# openTPM-v13.net
KiCad netlist of a schematic drawn in EAGLE
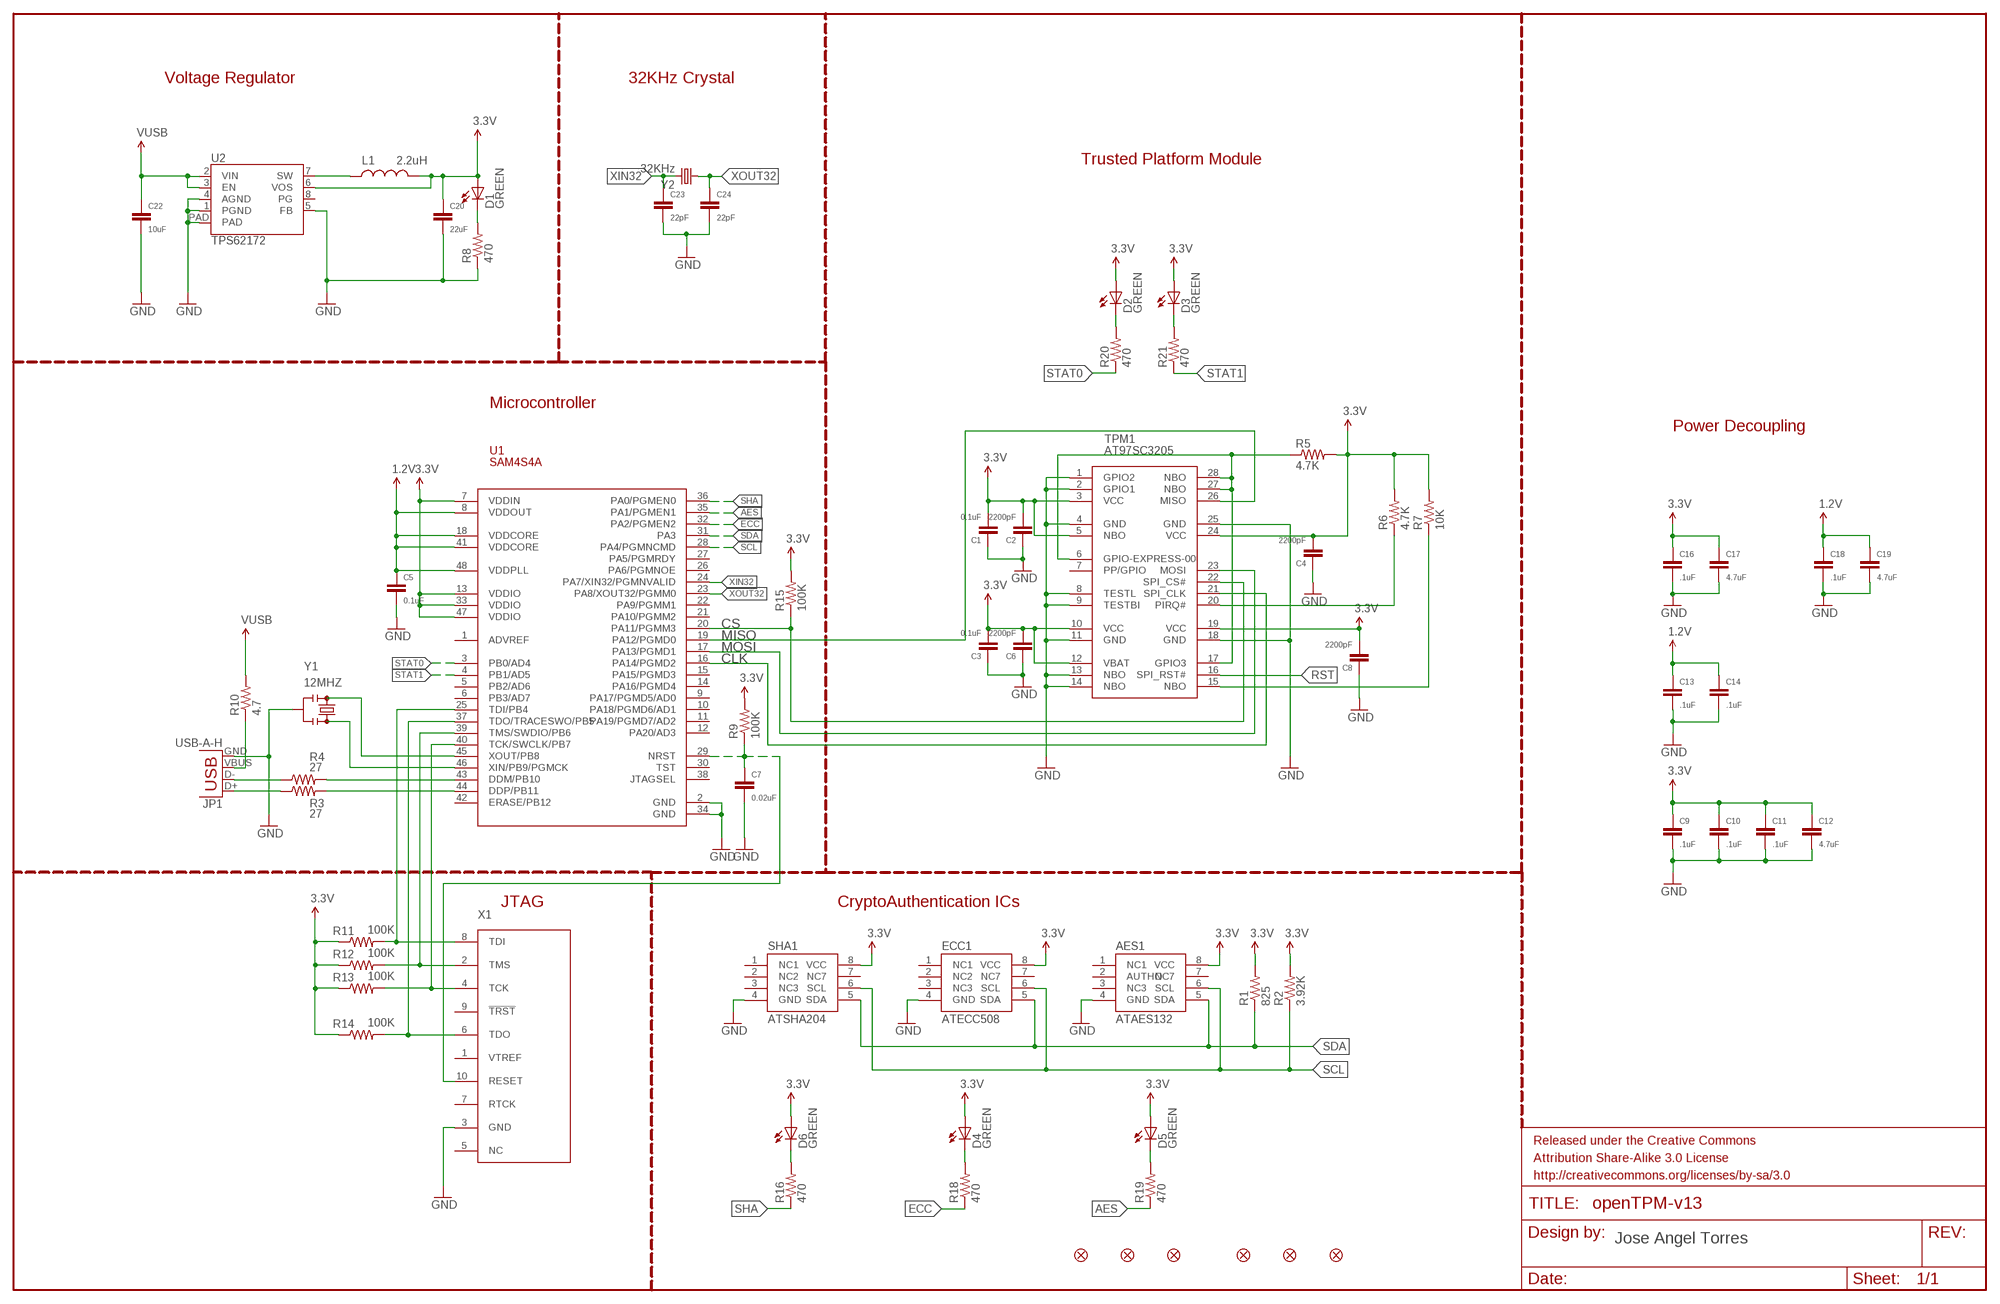
[diagram p0: schematic, sheet 1]

(export (version "E")
  (design (tool "Eeschema 10.0.6"))
  (components
    (comp (ref "AES1")
      (value "ATAES132")
      (footprint "eagle-import:CRYPTOTRONIX_SOIC8")
      (libsource (lib "eagle-import") (part "CRYPTOTRONIX_ATAES132"))
    )
    (comp (ref "C1")
      (value "0.1uF")
      (footprint "eagle-import:0201")
      (libsource (lib "eagle-import") (part "CAPACITOR.0201"))
    )
    (comp (ref "C2")
      (value "2200pF")
      (footprint "eagle-import:0201")
      (libsource (lib "eagle-import") (part "CAPACITOR.0201"))
    )
    (comp (ref "C3")
      (value "0.1uF")
      (footprint "eagle-import:0201")
      (libsource (lib "eagle-import") (part "CAPACITOR.0201"))
    )
    (comp (ref "C4")
      (value "2200pF")
      (footprint "eagle-import:0201")
      (libsource (lib "eagle-import") (part "CAPACITOR.0201"))
    )
    (comp (ref "C5")
      (value "0.1uF")
      (footprint "eagle-import:0201")
      (libsource (lib "eagle-import") (part "CAPACITOR.0201"))
    )
    (comp (ref "C6")
      (value "2200pF")
      (footprint "eagle-import:0201")
      (libsource (lib "eagle-import") (part "CAPACITOR.0201"))
    )
    (comp (ref "C7")
      (value "0.02uF")
      (footprint "eagle-import:0201")
      (libsource (lib "eagle-import") (part "CAPACITOR.0201"))
    )
    (comp (ref "C8")
      (value "2200pF")
      (footprint "eagle-import:0201")
      (libsource (lib "eagle-import") (part "CAPACITOR.0201"))
    )
    (comp (ref "C9")
      (value ".1uF")
      (footprint "eagle-import:0201")
      (libsource (lib "eagle-import") (part "CAPACITOR.0201"))
    )
    (comp (ref "C10")
      (value ".1uF")
      (footprint "eagle-import:0201")
      (libsource (lib "eagle-import") (part "CAPACITOR.0201"))
    )
    (comp (ref "C11")
      (value ".1uF")
      (footprint "eagle-import:0201")
      (libsource (lib "eagle-import") (part "CAPACITOR.0201"))
    )
    (comp (ref "C12")
      (value "4.7uF")
      (footprint "eagle-import:0402")
      (libsource (lib "eagle-import") (part "CAPACITOR.0402"))
    )
    (comp (ref "C13")
      (value ".1uF")
      (footprint "eagle-import:0201")
      (libsource (lib "eagle-import") (part "CAPACITOR.0201"))
    )
    (comp (ref "C14")
      (value ".1uF")
      (footprint "eagle-import:0201")
      (libsource (lib "eagle-import") (part "CAPACITOR.0201"))
    )
    (comp (ref "C16")
      (value ".1uF")
      (footprint "eagle-import:0201")
      (libsource (lib "eagle-import") (part "CAPACITOR.0201"))
    )
    (comp (ref "C17")
      (value "4.7uF")
      (footprint "eagle-import:0402")
      (libsource (lib "eagle-import") (part "CAPACITOR.0402"))
    )
    (comp (ref "C18")
      (value ".1uF")
      (footprint "eagle-import:0201")
      (libsource (lib "eagle-import") (part "CAPACITOR.0201"))
    )
    (comp (ref "C19")
      (value "4.7uF")
      (footprint "eagle-import:0402")
      (libsource (lib "eagle-import") (part "CAPACITOR.0402"))
    )
    (comp (ref "C20")
      (value "22uF")
      (footprint "eagle-import:0603")
      (libsource (lib "eagle-import") (part "CAPACITOR.0603"))
    )
    (comp (ref "C22")
      (value "10uF")
      (footprint "eagle-import:0402")
      (libsource (lib "eagle-import") (part "CAPACITOR.0402"))
    )
    (comp (ref "C23")
      (value "22pF")
      (footprint "eagle-import:0201")
      (libsource (lib "eagle-import") (part "CAPACITOR.0201"))
    )
    (comp (ref "C24")
      (value "22pF")
      (footprint "eagle-import:0201")
      (libsource (lib "eagle-import") (part "CAPACITOR.0201"))
    )
    (comp (ref "D1")
      (value "GREEN")
      (footprint "eagle-import:SPARKFUN-LED_LED-0603")
      (libsource (lib "eagle-import") (part "SPARKFUN-LED_LED-GREEN0603"))
    )
    (comp (ref "D2")
      (value "GREEN")
      (footprint "eagle-import:SPARKFUN-LED_LED-0603")
      (libsource (lib "eagle-import") (part "SPARKFUN-LED_LED-GREEN0603"))
    )
    (comp (ref "D3")
      (value "GREEN")
      (footprint "eagle-import:SPARKFUN-LED_LED-0603")
      (libsource (lib "eagle-import") (part "SPARKFUN-LED_LED-GREEN0603"))
    )
    (comp (ref "D4")
      (value "GREEN")
      (footprint "eagle-import:SPARKFUN-LED_LED-0603")
      (libsource (lib "eagle-import") (part "SPARKFUN-LED_LED-GREEN0603"))
    )
    (comp (ref "D5")
      (value "GREEN")
      (footprint "eagle-import:SPARKFUN-LED_LED-0603")
      (libsource (lib "eagle-import") (part "SPARKFUN-LED_LED-GREEN0603"))
    )
    (comp (ref "D6")
      (value "GREEN")
      (footprint "eagle-import:SPARKFUN-LED_LED-0603")
      (libsource (lib "eagle-import") (part "SPARKFUN-LED_LED-GREEN0603"))
    )
    (comp (ref "ECC1")
      (value "ATECC508")
      (footprint "eagle-import:CRYPTOTRONIX_SOIC8")
      (libsource (lib "eagle-import") (part "ATECC508"))
    )
    (comp (ref "FID1")
      (value "SPARKFUN-AESTHETICS_FIDUCIAL1X2")
      (footprint "eagle-import:SPARKFUN-AESTHETICS_FIDUCIAL-1X2")
      (libsource (lib "eagle-import") (part "SPARKFUN-AESTHETICS_FIDUCIAL1X2"))
    )
    (comp (ref "FID2")
      (value "SPARKFUN-AESTHETICS_FIDUCIAL1X2")
      (footprint "eagle-import:SPARKFUN-AESTHETICS_FIDUCIAL-1X2")
      (libsource (lib "eagle-import") (part "SPARKFUN-AESTHETICS_FIDUCIAL1X2"))
    )
    (comp (ref "FID3")
      (value "SPARKFUN-AESTHETICS_FIDUCIAL1X2")
      (footprint "eagle-import:SPARKFUN-AESTHETICS_FIDUCIAL-1X2")
      (libsource (lib "eagle-import") (part "SPARKFUN-AESTHETICS_FIDUCIAL1X2"))
    )
    (comp (ref "FID4")
      (value "SPARKFUN-AESTHETICS_FIDUCIAL1X2")
      (footprint "eagle-import:SPARKFUN-AESTHETICS_FIDUCIAL-1X2")
      (libsource (lib "eagle-import") (part "SPARKFUN-AESTHETICS_FIDUCIAL1X2"))
    )
    (comp (ref "FID5")
      (value "SPARKFUN-AESTHETICS_FIDUCIAL1X2")
      (footprint "eagle-import:SPARKFUN-AESTHETICS_FIDUCIAL-1X2")
      (libsource (lib "eagle-import") (part "SPARKFUN-AESTHETICS_FIDUCIAL1X2"))
    )
    (comp (ref "FID6")
      (value "SPARKFUN-AESTHETICS_FIDUCIAL1X2")
      (footprint "eagle-import:SPARKFUN-AESTHETICS_FIDUCIAL-1X2")
      (libsource (lib "eagle-import") (part "SPARKFUN-AESTHETICS_FIDUCIAL1X2"))
    )
    (comp (ref "JP1")
      (value "USB-A-H")
      (footprint "eagle-import:USB-A-H")
      (libsource (lib "eagle-import") (part "USB-A-H"))
    )
    (comp (ref "L1")
      (value "2.2uH")
      (footprint "eagle-import:C0402")
      (libsource (lib "eagle-import") (part "INDUCTOR0402"))
    )
    (comp (ref "R1")
      (value "825")
      (footprint "eagle-import:0201")
      (libsource (lib "eagle-import") (part "RESISTOR.0201"))
    )
    (comp (ref "R2")
      (value "3.92K")
      (footprint "eagle-import:0201")
      (libsource (lib "eagle-import") (part "RESISTOR.0201"))
    )
    (comp (ref "R3")
      (value "27")
      (footprint "eagle-import:0402")
      (libsource (lib "eagle-import") (part "RESISTOR.0402"))
    )
    (comp (ref "R4")
      (value "27")
      (footprint "eagle-import:0402")
      (libsource (lib "eagle-import") (part "RESISTOR.0402"))
    )
    (comp (ref "R5")
      (value "4.7K")
      (footprint "eagle-import:0201")
      (libsource (lib "eagle-import") (part "RESISTOR.0201"))
    )
    (comp (ref "R6")
      (value "4.7K")
      (footprint "eagle-import:0201")
      (libsource (lib "eagle-import") (part "RESISTOR.0201"))
    )
    (comp (ref "R7")
      (value "10K")
      (footprint "eagle-import:0201")
      (libsource (lib "eagle-import") (part "RESISTOR.0201"))
    )
    (comp (ref "R8")
      (value "470")
      (footprint "eagle-import:0201")
      (libsource (lib "eagle-import") (part "RESISTOR.0201"))
    )
    (comp (ref "R9")
      (value "100K")
      (footprint "eagle-import:0201")
      (libsource (lib "eagle-import") (part "RESISTOR.0201"))
    )
    (comp (ref "R10")
      (value "4.7")
      (footprint "eagle-import:0402")
      (libsource (lib "eagle-import") (part "RESISTOR.0402"))
    )
    (comp (ref "R11")
      (value "100K")
      (footprint "eagle-import:0201")
      (libsource (lib "eagle-import") (part "RESISTOR.0201"))
    )
    (comp (ref "R12")
      (value "100K")
      (footprint "eagle-import:0201")
      (libsource (lib "eagle-import") (part "RESISTOR.0201"))
    )
    (comp (ref "R13")
      (value "100K")
      (footprint "eagle-import:0201")
      (libsource (lib "eagle-import") (part "RESISTOR.0201"))
    )
    (comp (ref "R14")
      (value "100K")
      (footprint "eagle-import:0201")
      (libsource (lib "eagle-import") (part "RESISTOR.0201"))
    )
    (comp (ref "R15")
      (value "100K")
      (footprint "eagle-import:0201")
      (libsource (lib "eagle-import") (part "RESISTOR.0201"))
    )
    (comp (ref "R16")
      (value "470")
      (footprint "eagle-import:0201")
      (libsource (lib "eagle-import") (part "RESISTOR.0201"))
    )
    (comp (ref "R18")
      (value "470")
      (footprint "eagle-import:0201")
      (libsource (lib "eagle-import") (part "RESISTOR.0201"))
    )
    (comp (ref "R19")
      (value "470")
      (footprint "eagle-import:0201")
      (libsource (lib "eagle-import") (part "RESISTOR.0201"))
    )
    (comp (ref "R20")
      (value "470")
      (footprint "eagle-import:0201")
      (libsource (lib "eagle-import") (part "RESISTOR.0201"))
    )
    (comp (ref "R21")
      (value "470")
      (footprint "eagle-import:0201")
      (libsource (lib "eagle-import") (part "RESISTOR.0201"))
    )
    (comp (ref "SHA1")
      (value "ATSHA204")
      (footprint "eagle-import:CRYPTOTRONIX_SOIC8")
      (libsource (lib "eagle-import") (part "CRYPTOTRONIX_ATSHA204"))
    )
    (comp (ref "TPM1")
      (value "AT97SC3205")
      (footprint "eagle-import:TSSOP28")
      (libsource (lib "eagle-import") (part "AT97SC3205"))
    )
    (comp (ref "U1")
      (value "SAM4S4A")
      (footprint "eagle-import:LQFP-48")
      (libsource (lib "eagle-import") (part "SAM4S4A"))
    )
    (comp (ref "U2")
      (value "TPS62172")
      (footprint "eagle-import:WSON-8-PAD")
      (libsource (lib "eagle-import") (part "TPS62172"))
    )
    (comp (ref "X1")
      (value "TC2050-NL-MCP-NL")
      (footprint "eagle-import:TC2030-MCP-NL")
      (libsource (lib "eagle-import") (part "TC2050-NL-MCP-NL"))
    )
    (comp (ref "Y1")
      (value "12MHZ")
      (footprint "eagle-import:RESONATOR-SMD")
      (libsource (lib "eagle-import") (part "RESONATOR12MHZ"))
    )
    (comp (ref "Y2")
      (value "32KHz")
      (footprint "eagle-import:CRYSTAL-32KHZ-SMD_EPSON_MC146")
      (libsource (lib "eagle-import") (part "CRYSTALEPSONMC146"))
    )
  )
  (nets
    (net (code "1") (name "/CLK") (class "Default")
      (node (ref "TPM1") (pin "21") (pinfunction "SPI_CLK_21") (pintype "bidirectional"))
      (node (ref "U1") (pin "16") (pinfunction "PA14/PGMD2_16") (pintype "bidirectional"))
    )
    (net (code "2") (name "/CS") (class "Default")
      (node (ref "R15") (pin "1") (pinfunction "1_1") (pintype "passive"))
      (node (ref "TPM1") (pin "22") (pinfunction "SPI_CS#_22") (pintype "power_in"))
      (node (ref "U1") (pin "20") (pinfunction "PA11/PGMM3_20") (pintype "bidirectional"))
    )
    (net (code "3") (name "/MISO") (class "Default")
      (node (ref "TPM1") (pin "26") (pinfunction "MISO_26") (pintype "power_in"))
      (node (ref "U1") (pin "19") (pinfunction "PA12/PGMD0_19") (pintype "bidirectional"))
    )
    (net (code "4") (name "/MOSI") (class "Default")
      (node (ref "TPM1") (pin "23") (pinfunction "MOSI_23") (pintype "power_in"))
      (node (ref "U1") (pin "17") (pinfunction "PA13/PGMD1_17") (pintype "bidirectional"))
    )
    (net (code "5") (name "1.2V") (class "Default")
      (node (ref "C13") (pin "1") (pinfunction "1_1") (pintype "passive"))
      (node (ref "C14") (pin "1") (pinfunction "1_1") (pintype "passive"))
      (node (ref "C18") (pin "1") (pinfunction "1_1") (pintype "passive"))
      (node (ref "C19") (pin "1") (pinfunction "1_1") (pintype "passive"))
      (node (ref "C5") (pin "1") (pinfunction "1_1") (pintype "passive"))
      (node (ref "U1") (pin "18") (pinfunction "VDDCORE_18") (pintype "bidirectional"))
      (node (ref "U1") (pin "41") (pinfunction "VDDCORE_41") (pintype "bidirectional"))
      (node (ref "U1") (pin "48") (pinfunction "VDDPLL_48") (pintype "bidirectional"))
      (node (ref "U1") (pin "8") (pinfunction "VDDOUT_8") (pintype "bidirectional"))
    )
    (net (code "6") (name "3.3V") (class "Default")
      (node (ref "AES1") (pin "8") (pinfunction "VCC_8") (pintype "power_in"))
      (node (ref "C1") (pin "2") (pinfunction "2_2") (pintype "passive"))
      (node (ref "C10") (pin "1") (pinfunction "1_1") (pintype "passive"))
      (node (ref "C11") (pin "1") (pinfunction "1_1") (pintype "passive"))
      (node (ref "C12") (pin "1") (pinfunction "1_1") (pintype "passive"))
      (node (ref "C16") (pin "1") (pinfunction "1_1") (pintype "passive"))
      (node (ref "C17") (pin "1") (pinfunction "1_1") (pintype "passive"))
      (node (ref "C2") (pin "2") (pinfunction "2_2") (pintype "passive"))
      (node (ref "C20") (pin "1") (pinfunction "1_1") (pintype "passive"))
      (node (ref "C3") (pin "2") (pinfunction "2_2") (pintype "passive"))
      (node (ref "C4") (pin "2") (pinfunction "2_2") (pintype "passive"))
      (node (ref "C6") (pin "2") (pinfunction "2_2") (pintype "passive"))
      (node (ref "C8") (pin "2") (pinfunction "2_2") (pintype "passive"))
      (node (ref "C9") (pin "1") (pinfunction "1_1") (pintype "passive"))
      (node (ref "D1") (pin "A") (pinfunction "A_A") (pintype "passive"))
      (node (ref "D2") (pin "A") (pinfunction "A_A") (pintype "passive"))
      (node (ref "D3") (pin "A") (pinfunction "A_A") (pintype "passive"))
      (node (ref "D4") (pin "A") (pinfunction "A_A") (pintype "passive"))
      (node (ref "D5") (pin "A") (pinfunction "A_A") (pintype "passive"))
      (node (ref "D6") (pin "A") (pinfunction "A_A") (pintype "passive"))
      (node (ref "ECC1") (pin "8") (pinfunction "VCC_8") (pintype "power_in"))
      (node (ref "L1") (pin "2") (pinfunction "2_2") (pintype "passive"))
      (node (ref "R1") (pin "2") (pinfunction "2_2") (pintype "passive"))
      (node (ref "R11") (pin "1") (pinfunction "1_1") (pintype "passive"))
      (node (ref "R12") (pin "1") (pinfunction "1_1") (pintype "passive"))
      (node (ref "R13") (pin "1") (pinfunction "1_1") (pintype "passive"))
      (node (ref "R14") (pin "1") (pinfunction "1_1") (pintype "passive"))
      (node (ref "R15") (pin "2") (pinfunction "2_2") (pintype "passive"))
      (node (ref "R2") (pin "2") (pinfunction "2_2") (pintype "passive"))
      (node (ref "R5") (pin "2") (pinfunction "2_2") (pintype "passive"))
      (node (ref "R6") (pin "2") (pinfunction "2_2") (pintype "passive"))
      (node (ref "R7") (pin "2") (pinfunction "2_2") (pintype "passive"))
      (node (ref "R9") (pin "2") (pinfunction "2_2") (pintype "passive"))
      (node (ref "SHA1") (pin "8") (pinfunction "VCC_8") (pintype "power_in"))
      (node (ref "TPM1") (pin "10") (pinfunction "VCC_10") (pintype "power_in"))
      (node (ref "TPM1") (pin "12") (pinfunction "VBAT_12") (pintype "bidirectional"))
      (node (ref "TPM1") (pin "19") (pinfunction "VCC_19") (pintype "power_in"))
      (node (ref "TPM1") (pin "24") (pinfunction "VCC_24") (pintype "power_in"))
      (node (ref "TPM1") (pin "3") (pinfunction "VCC_3") (pintype "power_in"))
      (node (ref "TPM1") (pin "5") (pinfunction "NBO_5") (pintype "bidirectional"))
      (node (ref "U1") (pin "13") (pinfunction "VDDIO_13") (pintype "bidirectional"))
      (node (ref "U1") (pin "33") (pinfunction "VDDIO_33") (pintype "bidirectional"))
      (node (ref "U1") (pin "47") (pinfunction "VDDIO_47") (pintype "bidirectional"))
      (node (ref "U1") (pin "7") (pinfunction "VDDIN_7") (pintype "bidirectional"))
      (node (ref "U2") (pin "6") (pinfunction "VOS_6") (pintype "bidirectional"))
    )
    (net (code "7") (name "AES") (class "Default")
      (node (ref "R19") (pin "1") (pinfunction "1_1") (pintype "passive"))
      (node (ref "U1") (pin "35") (pinfunction "PA1/PGMEN1_35") (pintype "bidirectional"))
    )
    (net (code "8") (name "ECC") (class "Default")
      (node (ref "R18") (pin "1") (pinfunction "1_1") (pintype "passive"))
      (node (ref "U1") (pin "32") (pinfunction "PA2/PGMEN2_32") (pintype "bidirectional"))
    )
    (net (code "9") (name "GND") (class "Default")
      (node (ref "AES1") (pin "4") (pinfunction "GND_4") (pintype "power_in"))
      (node (ref "C1") (pin "1") (pinfunction "1_1") (pintype "passive"))
      (node (ref "C10") (pin "2") (pinfunction "2_2") (pintype "passive"))
      (node (ref "C11") (pin "2") (pinfunction "2_2") (pintype "passive"))
      (node (ref "C12") (pin "2") (pinfunction "2_2") (pintype "passive"))
      (node (ref "C13") (pin "2") (pinfunction "2_2") (pintype "passive"))
      (node (ref "C14") (pin "2") (pinfunction "2_2") (pintype "passive"))
      (node (ref "C16") (pin "2") (pinfunction "2_2") (pintype "passive"))
      (node (ref "C17") (pin "2") (pinfunction "2_2") (pintype "passive"))
      (node (ref "C18") (pin "2") (pinfunction "2_2") (pintype "passive"))
      (node (ref "C19") (pin "2") (pinfunction "2_2") (pintype "passive"))
      (node (ref "C2") (pin "1") (pinfunction "1_1") (pintype "passive"))
      (node (ref "C20") (pin "2") (pinfunction "2_2") (pintype "passive"))
      (node (ref "C22") (pin "2") (pinfunction "2_2") (pintype "passive"))
      (node (ref "C23") (pin "2") (pinfunction "2_2") (pintype "passive"))
      (node (ref "C24") (pin "2") (pinfunction "2_2") (pintype "passive"))
      (node (ref "C3") (pin "1") (pinfunction "1_1") (pintype "passive"))
      (node (ref "C4") (pin "1") (pinfunction "1_1") (pintype "passive"))
      (node (ref "C5") (pin "2") (pinfunction "2_2") (pintype "passive"))
      (node (ref "C6") (pin "1") (pinfunction "1_1") (pintype "passive"))
      (node (ref "C7") (pin "2") (pinfunction "2_2") (pintype "passive"))
      (node (ref "C8") (pin "1") (pinfunction "1_1") (pintype "passive"))
      (node (ref "C9") (pin "2") (pinfunction "2_2") (pintype "passive"))
      (node (ref "ECC1") (pin "4") (pinfunction "GND_4") (pintype "power_in"))
      (node (ref "JP1") (pin "GND") (pinfunction "GND_GND") (pintype "bidirectional"))
      (node (ref "R8") (pin "1") (pinfunction "1_1") (pintype "passive"))
      (node (ref "SHA1") (pin "4") (pinfunction "GND_4") (pintype "power_in"))
      (node (ref "TPM1") (pin "1") (pinfunction "GPIO2_1") (pintype "bidirectional"))
      (node (ref "TPM1") (pin "11") (pinfunction "GND_11") (pintype "power_in"))
      (node (ref "TPM1") (pin "13") (pinfunction "NBO_13") (pintype "bidirectional"))
      (node (ref "TPM1") (pin "14") (pinfunction "NBO_14") (pintype "bidirectional"))
      (node (ref "TPM1") (pin "18") (pinfunction "GND_18") (pintype "power_in"))
      (node (ref "TPM1") (pin "2") (pinfunction "GPIO1_2") (pintype "bidirectional"))
      (node (ref "TPM1") (pin "25") (pinfunction "GND_25") (pintype "power_in"))
      (node (ref "TPM1") (pin "4") (pinfunction "GND_4") (pintype "power_in"))
      (node (ref "TPM1") (pin "8") (pinfunction "TESTL_8") (pintype "bidirectional"))
      (node (ref "TPM1") (pin "9") (pinfunction "TESTBI_9") (pintype "bidirectional"))
      (node (ref "U1") (pin "2") (pinfunction "GND_2") (pintype "bidirectional"))
      (node (ref "U1") (pin "34") (pinfunction "GND_34") (pintype "bidirectional"))
      (node (ref "U2") (pin "1") (pinfunction "PGND_1") (pintype "bidirectional"))
      (node (ref "U2") (pin "4") (pinfunction "AGND_4") (pintype "bidirectional"))
      (node (ref "U2") (pin "5") (pinfunction "FB_5") (pintype "bidirectional"))
      (node (ref "U2") (pin "PAD") (pinfunction "PAD_PAD") (pintype "bidirectional"))
      (node (ref "X1") (pin "3") (pinfunction "GND_3") (pintype "bidirectional"))
      (node (ref "Y1") (pin "2") (pinfunction "2_2") (pintype "passive"))
    )
    (net (code "10") (name "Net-(D1-PadC)") (class "Default")
      (node (ref "D1") (pin "C") (pinfunction "C_C") (pintype "passive"))
      (node (ref "R8") (pin "2") (pinfunction "2_2") (pintype "passive"))
    )
    (net (code "11") (name "Net-(D2-PadC)") (class "Default")
      (node (ref "D2") (pin "C") (pinfunction "C_C") (pintype "passive"))
      (node (ref "R20") (pin "2") (pinfunction "2_2") (pintype "passive"))
    )
    (net (code "12") (name "Net-(D3-PadC)") (class "Default")
      (node (ref "D3") (pin "C") (pinfunction "C_C") (pintype "passive"))
      (node (ref "R21") (pin "2") (pinfunction "2_2") (pintype "passive"))
    )
    (net (code "13") (name "Net-(D4-PadC)") (class "Default")
      (node (ref "D4") (pin "C") (pinfunction "C_C") (pintype "passive"))
      (node (ref "R18") (pin "2") (pinfunction "2_2") (pintype "passive"))
    )
    (net (code "14") (name "Net-(D5-PadC)") (class "Default")
      (node (ref "D5") (pin "C") (pinfunction "C_C") (pintype "passive"))
      (node (ref "R19") (pin "2") (pinfunction "2_2") (pintype "passive"))
    )
    (net (code "15") (name "Net-(D6-PadC)") (class "Default")
      (node (ref "D6") (pin "C") (pinfunction "C_C") (pintype "passive"))
      (node (ref "R16") (pin "2") (pinfunction "2_2") (pintype "passive"))
    )
    (net (code "16") (name "Net-(JP1-PadD+)") (class "Default")
      (node (ref "JP1") (pin "D+") (pinfunction "D+_D+") (pintype "bidirectional"))
      (node (ref "R3") (pin "1") (pinfunction "1_1") (pintype "passive"))
    )
    (net (code "17") (name "Net-(JP1-PadD-)") (class "Default")
      (node (ref "JP1") (pin "D-") (pinfunction "D-_D-") (pintype "bidirectional"))
      (node (ref "R4") (pin "1") (pinfunction "1_1") (pintype "passive"))
    )
    (net (code "18") (name "Net-(JP1-PadVBUS)") (class "Default")
      (node (ref "JP1") (pin "VBUS") (pinfunction "VBUS_VBUS") (pintype "bidirectional"))
      (node (ref "R10") (pin "1") (pinfunction "1_1") (pintype "passive"))
    )
    (net (code "19") (name "Net-(R7-Pad1)") (class "Default")
      (node (ref "R7") (pin "1") (pinfunction "1_1") (pintype "passive"))
      (node (ref "TPM1") (pin "15") (pinfunction "NBO_15") (pintype "bidirectional"))
    )
    (net (code "20") (name "Net-(TPM1-GPIO-EXPRESS-00)") (class "Default")
      (node (ref "R5") (pin "1") (pinfunction "1_1") (pintype "passive"))
      (node (ref "TPM1") (pin "17") (pinfunction "GPIO3_17") (pintype "power_in"))
      (node (ref "TPM1") (pin "27") (pinfunction "NBO_27") (pintype "bidirectional"))
      (node (ref "TPM1") (pin "28") (pinfunction "NBO_28") (pintype "bidirectional"))
      (node (ref "TPM1") (pin "6") (pinfunction "GPIO-EXPRESS-00_6") (pintype "power_in"))
    )
    (net (code "21") (name "Net-(TPM1-PIRQ#)") (class "Default")
      (node (ref "R6") (pin "1") (pinfunction "1_1") (pintype "passive"))
      (node (ref "TPM1") (pin "20") (pinfunction "PIRQ#_20") (pintype "power_in"))
    )
    (net (code "22") (name "Net-(U1-DDM{slash}PB10)") (class "Default")
      (node (ref "R4") (pin "2") (pinfunction "2_2") (pintype "passive"))
      (node (ref "U1") (pin "43") (pinfunction "DDM/PB10_43") (pintype "bidirectional"))
    )
    (net (code "23") (name "Net-(U1-DDP{slash}PB11)") (class "Default")
      (node (ref "R3") (pin "2") (pinfunction "2_2") (pintype "passive"))
      (node (ref "U1") (pin "44") (pinfunction "DDP/PB11_44") (pintype "bidirectional"))
    )
    (net (code "24") (name "Net-(U1-TCK{slash}SWCLK{slash}PB7)") (class "Default")
      (node (ref "R13") (pin "2") (pinfunction "2_2") (pintype "passive"))
      (node (ref "U1") (pin "40") (pinfunction "TCK/SWCLK/PB7_40") (pintype "bidirectional"))
      (node (ref "X1") (pin "4") (pinfunction "TCK_4") (pintype "bidirectional"))
    )
    (net (code "25") (name "Net-(U1-TDI{slash}PB4)") (class "Default")
      (node (ref "R11") (pin "2") (pinfunction "2_2") (pintype "passive"))
      (node (ref "U1") (pin "25") (pinfunction "TDI/PB4_25") (pintype "bidirectional"))
      (node (ref "X1") (pin "8") (pinfunction "TDI_8") (pintype "bidirectional"))
    )
    (net (code "26") (name "Net-(U1-TDO{slash}TRACESWO{slash}PB5)") (class "Default")
      (node (ref "R14") (pin "2") (pinfunction "2_2") (pintype "passive"))
      (node (ref "U1") (pin "37") (pinfunction "TDO/TRACESWO/PB5_37") (pintype "bidirectional"))
      (node (ref "X1") (pin "6") (pinfunction "TDO_6") (pintype "bidirectional"))
    )
    (net (code "27") (name "Net-(U1-TMS{slash}SWDIO{slash}PB6)") (class "Default")
      (node (ref "R12") (pin "2") (pinfunction "2_2") (pintype "passive"))
      (node (ref "U1") (pin "39") (pinfunction "TMS/SWDIO/PB6_39") (pintype "bidirectional"))
      (node (ref "X1") (pin "2") (pinfunction "TMS_2") (pintype "bidirectional"))
    )
    (net (code "28") (name "Net-(U1-XIN{slash}PB9{slash}PGMCK)") (class "Default")
      (node (ref "U1") (pin "46") (pinfunction "XIN/PB9/PGMCK_46") (pintype "bidirectional"))
      (node (ref "Y1") (pin "3") (pinfunction "3_3") (pintype "passive"))
    )
    (net (code "29") (name "Net-(U1-XOUT{slash}PB8)") (class "Default")
      (node (ref "U1") (pin "45") (pinfunction "XOUT/PB8_45") (pintype "bidirectional"))
      (node (ref "Y1") (pin "1") (pinfunction "1_1") (pintype "passive"))
    )
    (net (code "30") (name "Net-(U2-SW)") (class "Default")
      (node (ref "L1") (pin "1") (pinfunction "1_1") (pintype "passive"))
      (node (ref "U2") (pin "7") (pinfunction "SW_7") (pintype "bidirectional"))
    )
    (net (code "31") (name "RST") (class "Default")
      (node (ref "C7") (pin "1") (pinfunction "1_1") (pintype "passive"))
      (node (ref "R9") (pin "1") (pinfunction "1_1") (pintype "passive"))
      (node (ref "TPM1") (pin "16") (pinfunction "SPI_RST#_16") (pintype "bidirectional"))
      (node (ref "U1") (pin "29") (pinfunction "NRST_29") (pintype "bidirectional"))
      (node (ref "X1") (pin "10") (pinfunction "RESET_10") (pintype "bidirectional"))
    )
    (net (code "32") (name "SCL") (class "Default")
      (node (ref "AES1") (pin "6") (pinfunction "SCL_6") (pintype "bidirectional"))
      (node (ref "ECC1") (pin "6") (pinfunction "SCL_6") (pintype "bidirectional"))
      (node (ref "R2") (pin "1") (pinfunction "1_1") (pintype "passive"))
      (node (ref "SHA1") (pin "6") (pinfunction "SCL_6") (pintype "bidirectional"))
      (node (ref "U1") (pin "28") (pinfunction "PA4/PGMNCMD_28") (pintype "bidirectional"))
    )
    (net (code "33") (name "SDA") (class "Default")
      (node (ref "AES1") (pin "5") (pinfunction "SDA_5") (pintype "bidirectional"))
      (node (ref "ECC1") (pin "5") (pinfunction "SDA_5") (pintype "bidirectional"))
      (node (ref "R1") (pin "1") (pinfunction "1_1") (pintype "passive"))
      (node (ref "SHA1") (pin "5") (pinfunction "SDA_5") (pintype "bidirectional"))
      (node (ref "U1") (pin "31") (pinfunction "PA3_31") (pintype "bidirectional"))
    )
    (net (code "34") (name "SHA") (class "Default")
      (node (ref "R16") (pin "1") (pinfunction "1_1") (pintype "passive"))
      (node (ref "U1") (pin "36") (pinfunction "PA0/PGMEN0_36") (pintype "bidirectional"))
    )
    (net (code "35") (name "STAT0") (class "Default")
      (node (ref "R20") (pin "1") (pinfunction "1_1") (pintype "passive"))
      (node (ref "U1") (pin "3") (pinfunction "PB0/AD4_3") (pintype "bidirectional"))
    )
    (net (code "36") (name "STAT1") (class "Default")
      (node (ref "R21") (pin "1") (pinfunction "1_1") (pintype "passive"))
      (node (ref "U1") (pin "4") (pinfunction "PB1/AD5_4") (pintype "bidirectional"))
    )
    (net (code "37") (name "VUSB") (class "Default")
      (node (ref "C22") (pin "1") (pinfunction "1_1") (pintype "passive"))
      (node (ref "R10") (pin "2") (pinfunction "2_2") (pintype "passive"))
      (node (ref "U2") (pin "2") (pinfunction "VIN_2") (pintype "bidirectional"))
      (node (ref "U2") (pin "3") (pinfunction "EN_3") (pintype "bidirectional"))
    )
    (net (code "38") (name "XIN32") (class "Default")
      (node (ref "C23") (pin "1") (pinfunction "1_1") (pintype "passive"))
      (node (ref "U1") (pin "24") (pinfunction "PA7/XIN32/PGMNVALID_24") (pintype "bidirectional"))
      (node (ref "Y2") (pin "P$1") (pinfunction "2_P$1") (pintype "passive"))
    )
    (net (code "39") (name "XOUT32") (class "Default")
      (node (ref "C24") (pin "1") (pinfunction "1_1") (pintype "passive"))
      (node (ref "U1") (pin "23") (pinfunction "PA8/XOUT32/PGMM0_23") (pintype "bidirectional"))
      (node (ref "Y2") (pin "P$2") (pinfunction "1_P$2") (pintype "passive"))
    )
    (net (code "40") (name "unconnected-(AES1-AUTHO-Pad2)") (class "Default")
      (node (ref "AES1") (pin "2") (pinfunction "AUTHO_2") (pintype "bidirectional"))
    )
    (net (code "41") (name "unconnected-(AES1-NC1-Pad1)") (class "Default")
      (node (ref "AES1") (pin "1") (pinfunction "NC1_1") (pintype "no_connect"))
    )
    (net (code "42") (name "unconnected-(AES1-NC3-Pad3)") (class "Default")
      (node (ref "AES1") (pin "3") (pinfunction "NC3_3") (pintype "no_connect"))
    )
    (net (code "43") (name "unconnected-(AES1-NC7-Pad7)") (class "Default")
      (node (ref "AES1") (pin "7") (pinfunction "NC7_7") (pintype "no_connect"))
    )
    (net (code "44") (name "unconnected-(ECC1-NC1-Pad1)") (class "Default")
      (node (ref "ECC1") (pin "1") (pinfunction "NC1_1") (pintype "bidirectional"))
    )
    (net (code "45") (name "unconnected-(ECC1-NC2-Pad2)") (class "Default")
      (node (ref "ECC1") (pin "2") (pinfunction "NC2_2") (pintype "no_connect"))
    )
    (net (code "46") (name "unconnected-(ECC1-NC3-Pad3)") (class "Default")
      (node (ref "ECC1") (pin "3") (pinfunction "NC3_3") (pintype "no_connect"))
    )
    (net (code "47") (name "unconnected-(ECC1-NC7-Pad7)") (class "Default")
      (node (ref "ECC1") (pin "7") (pinfunction "NC7_7") (pintype "no_connect"))
    )
    (net (code "48") (name "unconnected-(SHA1-NC1-Pad1)") (class "Default")
      (node (ref "SHA1") (pin "1") (pinfunction "NC1_1") (pintype "no_connect"))
    )
    (net (code "49") (name "unconnected-(SHA1-NC2-Pad2)") (class "Default")
      (node (ref "SHA1") (pin "2") (pinfunction "NC2_2") (pintype "no_connect"))
    )
    (net (code "50") (name "unconnected-(SHA1-NC3-Pad3)") (class "Default")
      (node (ref "SHA1") (pin "3") (pinfunction "NC3_3") (pintype "no_connect"))
    )
    (net (code "51") (name "unconnected-(SHA1-NC7-Pad7)") (class "Default")
      (node (ref "SHA1") (pin "7") (pinfunction "NC7_7") (pintype "no_connect"))
    )
    (net (code "52") (name "unconnected-(TPM1-PP{slash}GPIO-Pad7)") (class "Default")
      (node (ref "TPM1") (pin "7") (pinfunction "PP/GPIO_7") (pintype "bidirectional"))
    )
    (net (code "53") (name "unconnected-(U1-ADVREF-Pad1)") (class "Default")
      (node (ref "U1") (pin "1") (pinfunction "ADVREF_1") (pintype "bidirectional"))
    )
    (net (code "54") (name "unconnected-(U1-ERASE{slash}PB12-Pad42)") (class "Default")
      (node (ref "U1") (pin "42") (pinfunction "ERASE/PB12_42") (pintype "bidirectional"))
    )
    (net (code "55") (name "unconnected-(U1-JTAGSEL-Pad38)") (class "Default")
      (node (ref "U1") (pin "38") (pinfunction "JTAGSEL_38") (pintype "bidirectional"))
    )
    (net (code "56") (name "unconnected-(U1-PA5{slash}PGMRDY-Pad27)") (class "Default")
      (node (ref "U1") (pin "27") (pinfunction "PA5/PGMRDY_27") (pintype "bidirectional"))
    )
    (net (code "57") (name "unconnected-(U1-PA6{slash}PGMNOE-Pad26)") (class "Default")
      (node (ref "U1") (pin "26") (pinfunction "PA6/PGMNOE_26") (pintype "bidirectional"))
    )
    (net (code "58") (name "unconnected-(U1-PA9{slash}PGMM1-Pad22)") (class "Default")
      (node (ref "U1") (pin "22") (pinfunction "PA9/PGMM1_22") (pintype "bidirectional"))
    )
    (net (code "59") (name "unconnected-(U1-PA10{slash}PGMM2-Pad21)") (class "Default")
      (node (ref "U1") (pin "21") (pinfunction "PA10/PGMM2_21") (pintype "bidirectional"))
    )
    (net (code "60") (name "unconnected-(U1-PA15{slash}PGMD3-Pad15)") (class "Default")
      (node (ref "U1") (pin "15") (pinfunction "PA15/PGMD3_15") (pintype "bidirectional"))
    )
    (net (code "61") (name "unconnected-(U1-PA16{slash}PGMD4-Pad14)") (class "Default")
      (node (ref "U1") (pin "14") (pinfunction "PA16/PGMD4_14") (pintype "bidirectional"))
    )
    (net (code "62") (name "unconnected-(U1-PA17{slash}PGMD5{slash}AD0-Pad9)") (class "Default")
      (node (ref "U1") (pin "9") (pinfunction "PA17/PGMD5/AD0_9") (pintype "bidirectional"))
    )
    (net (code "63") (name "unconnected-(U1-PA18{slash}PGMD6{slash}AD1-Pad10)") (class "Default")
      (node (ref "U1") (pin "10") (pinfunction "PA18/PGMD6/AD1_10") (pintype "bidirectional"))
    )
    (net (code "64") (name "unconnected-(U1-PA19{slash}PGMD7{slash}AD2-Pad11)") (class "Default")
      (node (ref "U1") (pin "11") (pinfunction "PA19/PGMD7/AD2_11") (pintype "bidirectional"))
    )
    (net (code "65") (name "unconnected-(U1-PA20{slash}AD3-Pad12)") (class "Default")
      (node (ref "U1") (pin "12") (pinfunction "PA20/AD3_12") (pintype "bidirectional"))
    )
    (net (code "66") (name "unconnected-(U1-PB2{slash}AD6-Pad5)") (class "Default")
      (node (ref "U1") (pin "5") (pinfunction "PB2/AD6_5") (pintype "bidirectional"))
    )
    (net (code "67") (name "unconnected-(U1-PB3{slash}AD7-Pad6)") (class "Default")
      (node (ref "U1") (pin "6") (pinfunction "PB3/AD7_6") (pintype "bidirectional"))
    )
    (net (code "68") (name "unconnected-(U1-TST-Pad30)") (class "Default")
      (node (ref "U1") (pin "30") (pinfunction "TST_30") (pintype "bidirectional"))
    )
    (net (code "69") (name "unconnected-(U2-PG-Pad8)") (class "Default")
      (node (ref "U2") (pin "8") (pinfunction "PG_8") (pintype "bidirectional"))
    )
    (net (code "70") (name "unconnected-(X1-NC-Pad5)") (class "Default")
      (node (ref "X1") (pin "5") (pinfunction "NC_5") (pintype "bidirectional"))
    )
    (net (code "71") (name "unconnected-(X1-RTCK-Pad7)") (class "Default")
      (node (ref "X1") (pin "7") (pinfunction "RTCK_7") (pintype "bidirectional"))
    )
    (net (code "72") (name "unconnected-(X1-VTREF-Pad1)") (class "Default")
      (node (ref "X1") (pin "1") (pinfunction "VTREF_1") (pintype "bidirectional"))
    )
    (net (code "73") (name "unconnected-(X1-~{TRST}-Pad9)") (class "Default")
      (node (ref "X1") (pin "9") (pinfunction "~{TRST}_9") (pintype "bidirectional"))
    )
  )
)
